# MCU_Programmer.net
KiCad netlist of a schematic drawn in Altium Designer
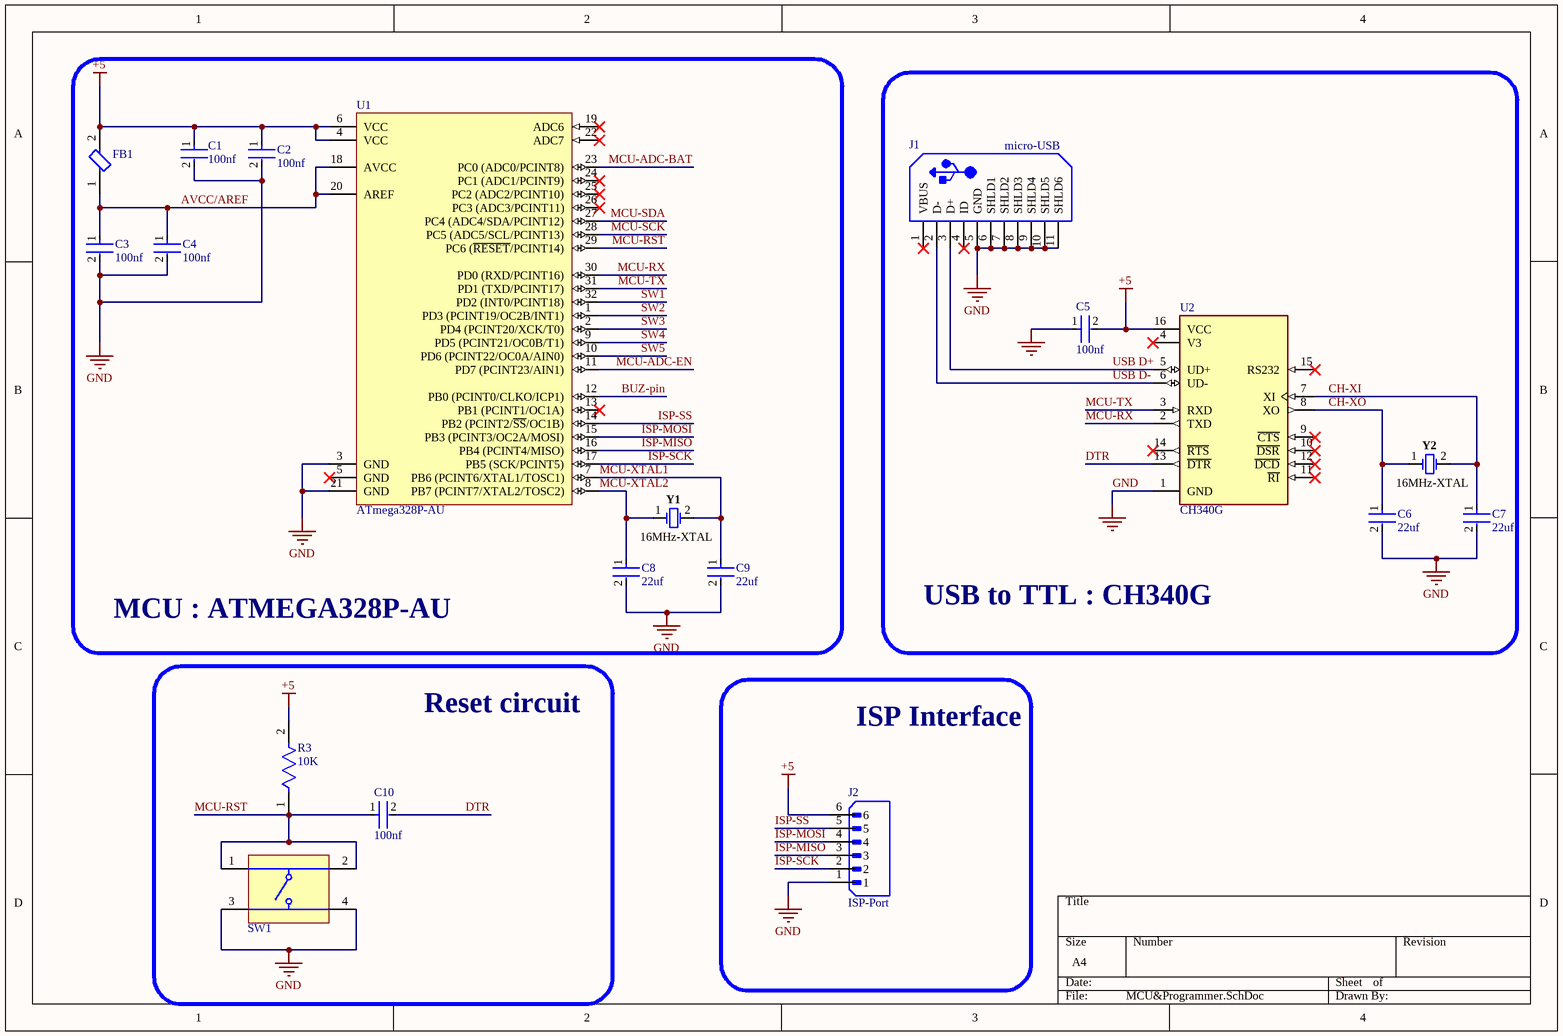
[diagram p0: MCU&Programmer.SchDoc]

(export (version "E")
  (design (tool "Eeschema 10.0.6"))
  (components
    (comp (ref "C1")
      (value "100nf")
      (footprint "FP-CC0805-0_85-MFG")
      (description "CAP CER 0.1UF 50V X7R 0805")
      (fields (field (name "TOLERANCE") "0.1") (field (name "MANUFACTURER PART NUMBER") "CC0805KRX7R9BB104"))
      (libsource (lib "Altium Content Vault") (part "11868f565c42a9108669ba33697ecf6"))
    )
    (comp (ref "C2")
      (value "100nf")
      (footprint "FP-CC0805-0_85-MFG")
      (description "CAP CER 0.1UF 50V X7R 0805")
      (fields (field (name "TOLERANCE") "0.1") (field (name "MANUFACTURER PART NUMBER") "CC0805KRX7R9BB104"))
      (libsource (lib "Altium Content Vault") (part "11868f565c42a9108669ba33697ecf6"))
    )
    (comp (ref "C3")
      (value "100nf")
      (footprint "FP-CC0805-0_85-MFG")
      (description "CAP CER 0.1UF 50V X7R 0805")
      (fields (field (name "TOLERANCE") "0.1") (field (name "MANUFACTURER PART NUMBER") "CC0805KRX7R9BB104"))
      (libsource (lib "Altium Content Vault") (part "11868f565c42a9108669ba33697ecf6"))
    )
    (comp (ref "C4")
      (value "100nf")
      (footprint "FP-CC0805-0_85-MFG")
      (description "CAP CER 0.1UF 50V X7R 0805")
      (fields (field (name "TOLERANCE") "0.1") (field (name "MANUFACTURER PART NUMBER") "CC0805KRX7R9BB104"))
      (libsource (lib "Altium Content Vault") (part "11868f565c42a9108669ba33697ecf6"))
    )
    (comp (ref "C5")
      (value "100nf")
      (footprint "FP-CC0805-0_85-MFG")
      (description "CAP CER 0.1UF 50V X7R 0805")
      (fields (field (name "TOLERANCE") "0.1") (field (name "MANUFACTURER PART NUMBER") "CC0805KRX7R9BB104"))
      (libsource (lib "Altium Content Vault") (part "11868f565c42a9108669ba33697ecf6"))
    )
    (comp (ref "C6")
      (value "22uf")
      (footprint "FP-CC0805-0_85-MFG")
      (description "CAP CER 0.1UF 50V X7R 0805")
      (fields (field (name "TOLERANCE") "0.1") (field (name "MANUFACTURER PART NUMBER") "CC0805KRX7R9BB104"))
      (libsource (lib "Altium Content Vault") (part "11868f565c42a9108669ba33697ecf6"))
    )
    (comp (ref "C7")
      (value "22uf")
      (footprint "FP-CC0805-0_85-MFG")
      (description "CAP CER 0.1UF 50V X7R 0805")
      (fields (field (name "TOLERANCE") "0.1") (field (name "MANUFACTURER PART NUMBER") "CC0805KRX7R9BB104"))
      (libsource (lib "Altium Content Vault") (part "11868f565c42a9108669ba33697ecf6"))
    )
    (comp (ref "C8")
      (value "22uf")
      (footprint "FP-CC0805-0_85-MFG")
      (description "CAP CER 0.1UF 50V X7R 0805")
      (fields (field (name "TOLERANCE") "0.1") (field (name "MANUFACTURER PART NUMBER") "CC0805KRX7R9BB104"))
      (libsource (lib "Altium Content Vault") (part "11868f565c42a9108669ba33697ecf6"))
    )
    (comp (ref "C9")
      (value "22uf")
      (footprint "FP-CC0805-0_85-MFG")
      (description "CAP CER 0.1UF 50V X7R 0805")
      (fields (field (name "TOLERANCE") "0.1") (field (name "MANUFACTURER PART NUMBER") "CC0805KRX7R9BB104"))
      (libsource (lib "Altium Content Vault") (part "11868f565c42a9108669ba33697ecf6"))
    )
    (comp (ref "C10")
      (value "100nf")
      (footprint "FP-CC0805-0_85-MFG")
      (description "CAP CER 0.1UF 50V X7R 0805")
      (fields (field (name "TOLERANCE") "0.1") (field (name "MANUFACTURER PART NUMBER") "CC0805KRX7R9BB104"))
      (libsource (lib "Altium Content Vault") (part "11868f565c42a9108669ba33697ecf6"))
    )
    (comp (ref "FB1")
      (value "~")
      (footprint "FP-BLM21-0_2-t0_85-e0_5-IPC_B")
      (description "Chip Ferrite Bead, 0805, 220Ω @ 100MHz, 0.045Ω, 25%, 2A")
      (fields (field (name "TOLERANCE") "25%"))
      (libsource (lib "Altium Content Vault") (part "5f30dd21d616792df468990f7003faa"))
    )
    (comp (ref "J1")
      (value "micro-USB")
      (footprint "USB-MICRO-B_V")
      (fields (field (name "MANUFACTURER") "Molex"))
      (libsource (lib "Altium Content Vault") (part "USB-5-6SHLD"))
    )
    (comp (ref "J2")
      (value "ISP-Port")
      (footprint "JST_B6B-XH-A(LF)(SN)")
      (description "Connector Header Through Hole 6 position 0.098 (2.50mm)")
      (fields (field (name "MF") "JST Sales") (field (name "MP") "B6B-XH-A(LF)(SN)"))
      (libsource (lib "B6B-XH-A_LF__SN_") (part "B6B-XH-A(LF)(SN)"))
    )
    (comp (ref "R3")
      (value "10K")
      (footprint "FP-CRCW0805-e3-MFG")
      (description "RES Thick Film, 100kΩ, 1%, 0.125W, 100ppm/°C, 0805")
      (fields (field (name "TOLERANCE") "1%"))
      (libsource (lib "Altium Content Vault") (part "1029c3af85768c4190bb7ad29bc67b5"))
    )
    (comp (ref "SW1")
      (value "FSM4JSMATR")
      (footprint "TECO-FSM4JSMATR_V")
      (description "Micro Miniature Push Button Switch FSM JSM, 50 mA, -35 to 85 degC, 4-Pin SMD, RoHS, Tape and Reel")
      (fields (field (name "MANUFACTURER") "TE Connectivity"))
      (libsource (lib "Altium Content Vault") (part "SW-SPST-4_A"))
    )
    (comp (ref "U1")
      (value "ATmega328P-AU")
      (footprint "32A_M")
      (libsource (lib "Altium Content Vault") (part "MC-8B-ATM48-SQ32"))
    )
    (comp (ref "U2")
      (value "CH340G")
      (footprint "SOIC127P600X180-16N")
      (description "USB Interface Integrated Circuit")
      (fields (field (name "MP") "Ch340G") (field (name "MF") "WCH"))
      (libsource (lib "CH340G") (part "CH340G"))
    )
    (comp (ref "Y1")
      (value "16MHz-XTAL")
      (footprint "FOX-FOXSLF160-20")
      (description "Resistance Weld Thru-Hole Crystal, 16 MHz, -20 to 70 degC, 2-Pin THD, RoHS, Bulk")
      (fields (field (name "TOLERANCE") "1%"))
      (libsource (lib "Altium Content Vault") (part "XTAL-1-2-2"))
    )
    (comp (ref "Y2")
      (value "16MHz-XTAL")
      (footprint "FOX-FOXSLF160-20")
      (description "Resistance Weld Thru-Hole Crystal, 16 MHz, -20 to 70 degC, 2-Pin THD, RoHS, Bulk")
      (fields (field (name "TOLERANCE") "1%"))
      (libsource (lib "Altium Content Vault") (part "XTAL-1-2-2"))
    )
  )
  (nets
    (net (code "1") (name "+5") (class "Default")
      (node (ref "C1") (pin "1") (pinfunction "1_1") (pintype "passive"))
      (node (ref "C2") (pin "1") (pinfunction "1_1") (pintype "passive"))
      (node (ref "C5") (pin "2") (pinfunction "2_2") (pintype "passive"))
      (node (ref "FB1") (pin "2") (pinfunction "2_2") (pintype "passive"))
      (node (ref "J2") (pin "6") (pinfunction "6_6") (pintype "passive"))
      (node (ref "R3") (pin "2") (pinfunction "2_2") (pintype "passive"))
      (node (ref "U1") (pin "4") (pinfunction "VCC_4") (pintype "power_in"))
      (node (ref "U1") (pin "6") (pinfunction "VCC_6") (pintype "power_in"))
      (node (ref "U2") (pin "16") (pinfunction "VCC_16") (pintype "power_in"))
    )
    (net (code "2") (name "/AVCC{slash}AREF") (class "Default")
      (node (ref "C3") (pin "1") (pinfunction "1_1") (pintype "passive"))
      (node (ref "C4") (pin "1") (pinfunction "1_1") (pintype "passive"))
      (node (ref "FB1") (pin "1") (pinfunction "1_1") (pintype "passive"))
      (node (ref "U1") (pin "18") (pinfunction "AVCC_18") (pintype "power_in"))
      (node (ref "U1") (pin "20") (pinfunction "AREF_20") (pintype "passive"))
    )
    (net (code "3") (name "/BUZ-pin") (class "Default")
      (node (ref "U1") (pin "12") (pinfunction "PB0_(PCINT0/CLKO/ICP1)_12") (pintype "bidirectional"))
    )
    (net (code "4") (name "/CH-XI") (class "Default")
      (node (ref "C7") (pin "1") (pinfunction "1_1") (pintype "passive"))
      (node (ref "U2") (pin "7") (pinfunction "XI_7") (pintype "input"))
      (node (ref "Y2") (pin "2") (pinfunction "2_2") (pintype "passive"))
    )
    (net (code "5") (name "/CH-XO") (class "Default")
      (node (ref "C6") (pin "1") (pinfunction "1_1") (pintype "passive"))
      (node (ref "U2") (pin "8") (pinfunction "XO_8") (pintype "output"))
      (node (ref "Y2") (pin "1") (pinfunction "1_1") (pintype "passive"))
    )
    (net (code "6") (name "/DTR") (class "Default")
      (node (ref "C10") (pin "2") (pinfunction "2_2") (pintype "passive"))
      (node (ref "U2") (pin "13") (pinfunction "~{DTR}_13") (pintype "output"))
    )
    (net (code "7") (name "/ISP-MISO") (class "Default")
      (node (ref "J2") (pin "3") (pinfunction "3_3") (pintype "passive"))
      (node (ref "U1") (pin "16") (pinfunction "PB4_(PCINT4/MISO)_16") (pintype "bidirectional"))
    )
    (net (code "8") (name "/ISP-MOSI") (class "Default")
      (node (ref "J2") (pin "4") (pinfunction "4_4") (pintype "passive"))
      (node (ref "U1") (pin "15") (pinfunction "PB3_(PCINT3/OC2A/MOSI)_15") (pintype "bidirectional"))
    )
    (net (code "9") (name "/ISP-SCK") (class "Default")
      (node (ref "J2") (pin "2") (pinfunction "2_2") (pintype "passive"))
      (node (ref "U1") (pin "17") (pinfunction "PB5_(SCK/PCINT5)_17") (pintype "bidirectional"))
    )
    (net (code "10") (name "/ISP-SS") (class "Default")
      (node (ref "J2") (pin "5") (pinfunction "5_5") (pintype "passive"))
      (node (ref "U1") (pin "14") (pinfunction "PB2_(PCINT2/~{SS}/OC1B)_14") (pintype "bidirectional"))
    )
    (net (code "11") (name "/MCU-ADC-BAT") (class "Default")
      (node (ref "U1") (pin "23") (pinfunction "PC0_(ADC0/PCINT8)_23") (pintype "bidirectional"))
    )
    (net (code "12") (name "/MCU-ADC-EN") (class "Default")
      (node (ref "U1") (pin "11") (pinfunction "PD7_(PCINT23/AIN1)_11") (pintype "bidirectional"))
    )
    (net (code "13") (name "/MCU-RST") (class "Default")
      (node (ref "C10") (pin "1") (pinfunction "1_1") (pintype "passive"))
      (node (ref "R3") (pin "1") (pinfunction "1_1") (pintype "passive"))
      (node (ref "SW1") (pin "1") (pinfunction "1_1") (pintype "passive"))
      (node (ref "SW1") (pin "2") (pinfunction "2_2") (pintype "passive"))
      (node (ref "U1") (pin "29") (pinfunction "PC6_(~{RESET}/PCINT14)_29") (pintype "bidirectional"))
    )
    (net (code "14") (name "/MCU-RX") (class "Default")
      (node (ref "U1") (pin "30") (pinfunction "PD0_(RXD/PCINT16)_30") (pintype "bidirectional"))
      (node (ref "U2") (pin "2") (pinfunction "TXD_2") (pintype "output"))
    )
    (net (code "15") (name "/MCU-SCK") (class "Default")
      (node (ref "U1") (pin "28") (pinfunction "PC5_(ADC5/SCL/PCINT13)_28") (pintype "bidirectional"))
    )
    (net (code "16") (name "/MCU-SDA") (class "Default")
      (node (ref "U1") (pin "27") (pinfunction "PC4_(ADC4/SDA/PCINT12)_27") (pintype "bidirectional"))
    )
    (net (code "17") (name "/MCU-TX") (class "Default")
      (node (ref "U1") (pin "31") (pinfunction "PD1_(TXD/PCINT17)_31") (pintype "bidirectional"))
      (node (ref "U2") (pin "3") (pinfunction "RXD_3") (pintype "input"))
    )
    (net (code "18") (name "/MCU-XTAL1") (class "Default")
      (node (ref "C9") (pin "1") (pinfunction "1_1") (pintype "passive"))
      (node (ref "U1") (pin "7") (pinfunction "PB6_(PCINT6/XTAL1/TOSC1)_7") (pintype "bidirectional"))
      (node (ref "Y1") (pin "2") (pinfunction "2_2") (pintype "passive"))
    )
    (net (code "19") (name "/MCU-XTAL2") (class "Default")
      (node (ref "C8") (pin "1") (pinfunction "1_1") (pintype "passive"))
      (node (ref "U1") (pin "8") (pinfunction "PB7_(PCINT7/XTAL2/TOSC2)_8") (pintype "bidirectional"))
      (node (ref "Y1") (pin "1") (pinfunction "1_1") (pintype "passive"))
    )
    (net (code "20") (name "/SW1") (class "Default")
      (node (ref "U1") (pin "32") (pinfunction "PD2_(INT0/PCINT18)_32") (pintype "bidirectional"))
    )
    (net (code "21") (name "/SW2") (class "Default")
      (node (ref "U1") (pin "1") (pinfunction "PD3_(PCINT19/OC2B/INT1)_1") (pintype "bidirectional"))
    )
    (net (code "22") (name "/SW3") (class "Default")
      (node (ref "U1") (pin "2") (pinfunction "PD4_(PCINT20/XCK/T0)_2") (pintype "bidirectional"))
    )
    (net (code "23") (name "/SW4") (class "Default")
      (node (ref "U1") (pin "9") (pinfunction "PD5_(PCINT21/OC0B/T1)_9") (pintype "bidirectional"))
    )
    (net (code "24") (name "/SW5") (class "Default")
      (node (ref "U1") (pin "10") (pinfunction "PD6_(PCINT22/OC0A/AIN0)_10") (pintype "bidirectional"))
    )
    (net (code "25") (name "/USB D+") (class "Default")
      (node (ref "J1") (pin "3") (pinfunction "D+_3") (pintype "passive"))
      (node (ref "U2") (pin "5") (pinfunction "UD+_5") (pintype "bidirectional"))
    )
    (net (code "26") (name "/USB D-") (class "Default")
      (node (ref "J1") (pin "2") (pinfunction "D-_2") (pintype "passive"))
      (node (ref "U2") (pin "6") (pinfunction "UD-_6") (pintype "bidirectional"))
    )
    (net (code "27") (name "GND") (class "Default")
      (node (ref "C1") (pin "2") (pinfunction "2_2") (pintype "passive"))
      (node (ref "C2") (pin "2") (pinfunction "2_2") (pintype "passive"))
      (node (ref "C3") (pin "2") (pinfunction "2_2") (pintype "passive"))
      (node (ref "C4") (pin "2") (pinfunction "2_2") (pintype "passive"))
      (node (ref "C5") (pin "1") (pinfunction "1_1") (pintype "passive"))
      (node (ref "C6") (pin "2") (pinfunction "2_2") (pintype "passive"))
      (node (ref "C7") (pin "2") (pinfunction "2_2") (pintype "passive"))
      (node (ref "C8") (pin "2") (pinfunction "2_2") (pintype "passive"))
      (node (ref "C9") (pin "2") (pinfunction "2_2") (pintype "passive"))
      (node (ref "J1") (pin "10") (pinfunction "SHLD5_10") (pintype "passive"))
      (node (ref "J1") (pin "11") (pinfunction "SHLD6_11") (pintype "passive"))
      (node (ref "J1") (pin "5") (pinfunction "GND_5") (pintype "passive"))
      (node (ref "J1") (pin "6") (pinfunction "SHLD1_6") (pintype "passive"))
      (node (ref "J1") (pin "7") (pinfunction "SHLD2_7") (pintype "passive"))
      (node (ref "J1") (pin "8") (pinfunction "SHLD3_8") (pintype "passive"))
      (node (ref "J1") (pin "9") (pinfunction "SHLD4_9") (pintype "passive"))
      (node (ref "J2") (pin "1") (pinfunction "1_1") (pintype "passive"))
      (node (ref "SW1") (pin "3") (pinfunction "3_3") (pintype "passive"))
      (node (ref "SW1") (pin "4") (pinfunction "4_4") (pintype "passive"))
      (node (ref "U1") (pin "21") (pinfunction "GND_21") (pintype "power_in"))
      (node (ref "U1") (pin "3") (pinfunction "GND_3") (pintype "power_in"))
      (node (ref "U2") (pin "1") (pinfunction "GND_1") (pintype "power_in"))
    )
    (net (code "28") (name "unconnected-(J1-ID-Pad4)") (class "Default")
      (node (ref "J1") (pin "4") (pinfunction "ID_4") (pintype "passive+no_connect"))
    )
    (net (code "29") (name "unconnected-(J1-VBUS-Pad1)") (class "Default")
      (node (ref "J1") (pin "1") (pinfunction "VBUS_1") (pintype "passive+no_connect"))
    )
    (net (code "30") (name "unconnected-(U1-ADC6-Pad19)") (class "Default")
      (node (ref "U1") (pin "19") (pinfunction "ADC6_19") (pintype "input+no_connect"))
    )
    (net (code "31") (name "unconnected-(U1-ADC7-Pad22)") (class "Default")
      (node (ref "U1") (pin "22") (pinfunction "ADC7_22") (pintype "input+no_connect"))
    )
    (net (code "32") (name "unconnected-(U1-GND-Pad5)") (class "Default")
      (node (ref "U1") (pin "5") (pinfunction "GND_5") (pintype "power_in+no_connect"))
    )
    (net (code "33") (name "unconnected-(U1-PB1_(PCINT1{slash}OC1A)-Pad13)") (class "Default")
      (node (ref "U1") (pin "13") (pinfunction "PB1_(PCINT1/OC1A)_13") (pintype "bidirectional+no_connect"))
    )
    (net (code "34") (name "unconnected-(U1-PC1_(ADC1{slash}PCINT9)-Pad24)") (class "Default")
      (node (ref "U1") (pin "24") (pinfunction "PC1_(ADC1/PCINT9)_24") (pintype "bidirectional+no_connect"))
    )
    (net (code "35") (name "unconnected-(U1-PC2_(ADC2{slash}PCINT10)-Pad25)") (class "Default")
      (node (ref "U1") (pin "25") (pinfunction "PC2_(ADC2/PCINT10)_25") (pintype "bidirectional+no_connect"))
    )
    (net (code "36") (name "unconnected-(U1-PC3_(ADC3{slash}PCINT11)-Pad26)") (class "Default")
      (node (ref "U1") (pin "26") (pinfunction "PC3_(ADC3/PCINT11)_26") (pintype "bidirectional+no_connect"))
    )
    (net (code "37") (name "unconnected-(U2-RS232-Pad15)") (class "Default")
      (node (ref "U2") (pin "15") (pinfunction "RS232_15") (pintype "input+no_connect"))
    )
    (net (code "38") (name "unconnected-(U2-V3-Pad4)") (class "Default")
      (node (ref "U2") (pin "4") (pinfunction "V3_4") (pintype "power_in+no_connect"))
    )
    (net (code "39") (name "unconnected-(U2-~{CTS}-Pad9)") (class "Default")
      (node (ref "U2") (pin "9") (pinfunction "~{CTS}_9") (pintype "input+no_connect"))
    )
    (net (code "40") (name "unconnected-(U2-~{DCD}-Pad12)") (class "Default")
      (node (ref "U2") (pin "12") (pinfunction "~{DCD}_12") (pintype "input+no_connect"))
    )
    (net (code "41") (name "unconnected-(U2-~{DSR}-Pad10)") (class "Default")
      (node (ref "U2") (pin "10") (pinfunction "~{DSR}_10") (pintype "input+no_connect"))
    )
    (net (code "42") (name "unconnected-(U2-~{RI}-Pad11)") (class "Default")
      (node (ref "U2") (pin "11") (pinfunction "~{RI}_11") (pintype "input+no_connect"))
    )
    (net (code "43") (name "unconnected-(U2-~{RTS}-Pad14)") (class "Default")
      (node (ref "U2") (pin "14") (pinfunction "~{RTS}_14") (pintype "output+no_connect"))
    )
  )
)
